# IMU.net
KiCad netlist of a schematic drawn in Altium Designer
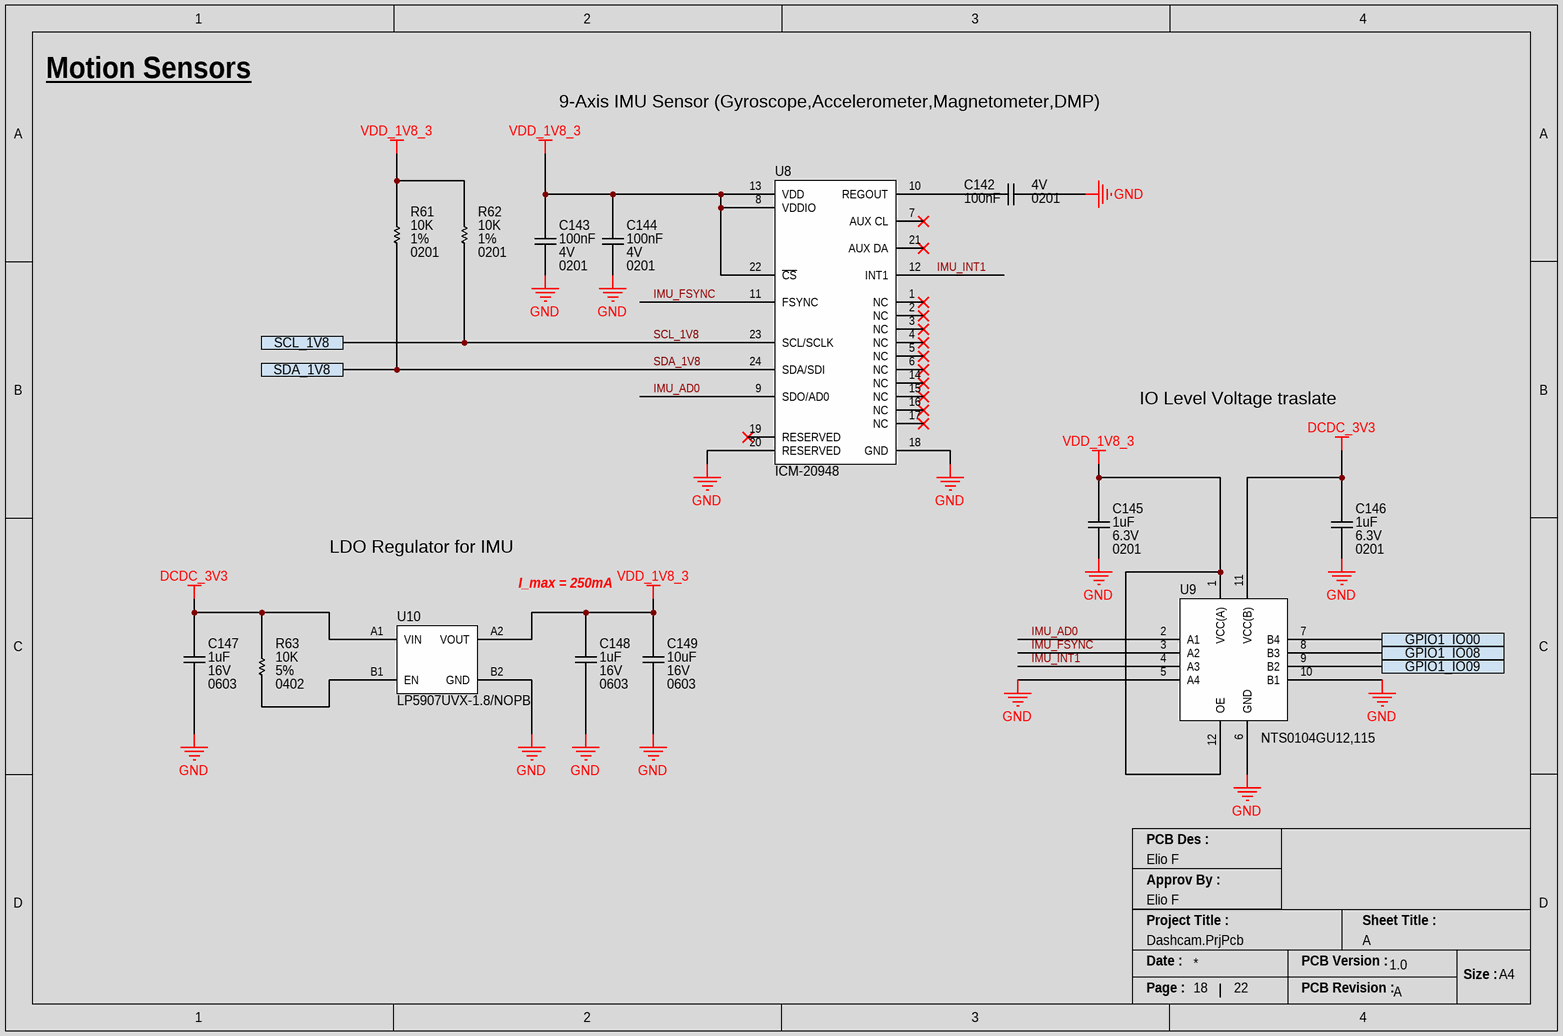
[diagram p0: IMU.SchDoc]

(export (version "E")
  (design (tool "Eeschema 10.0.6"))
  (components
    (comp (ref "C142")
      (value "C0201C104K7PAC7867")
      (footprint "CAP_0201_CAPC0603X03N")
      (description "SMD Comm X5R 0201 (0603Metric) ceramic capacitor 0.024Lx0.012W 0.60mmx0.30mm X5R ±10% 0.1muF")
      (fields
        (field (name "MANUFACTURER") "KEMET")
        (field (name "TOLERANCE") "10%")
        (field (name "VOLTAGE RATING") "4V")
        (field (name "CAPACITANCE") "100nF")
        (field (name "CASE/PACKAGE") "0201")
      )
      (libsource (lib "Electronic Devices_LIB") (part "CAP_100NF_4V_X5R_0201"))
    )
    (comp (ref "C143")
      (value "C0201C104K7PAC7867")
      (footprint "CAP_0201_CAPC0603X03N")
      (description "SMD Comm X5R 0201 (0603Metric) ceramic capacitor 0.024Lx0.012W 0.60mmx0.30mm X5R ±10% 0.1muF")
      (fields
        (field (name "MANUFACTURER") "KEMET")
        (field (name "TOLERANCE") "10%")
        (field (name "VOLTAGE RATING") "4V")
        (field (name "CAPACITANCE") "100nF")
        (field (name "CASE/PACKAGE") "0201")
      )
      (libsource (lib "Electronic Devices_LIB") (part "CAP_100NF_4V_X5R_0201"))
    )
    (comp (ref "C144")
      (value "C0201C104K7PAC7867")
      (footprint "CAP_0201_CAPC0603X03N")
      (description "SMD Comm X5R 0201 (0603Metric) ceramic capacitor 0.024Lx0.012W 0.60mmx0.30mm X5R ±10% 0.1muF")
      (fields
        (field (name "MANUFACTURER") "KEMET")
        (field (name "TOLERANCE") "10%")
        (field (name "VOLTAGE RATING") "4V")
        (field (name "CAPACITANCE") "100nF")
        (field (name "CASE/PACKAGE") "0201")
      )
      (libsource (lib "Electronic Devices_LIB") (part "CAP_100NF_4V_X5R_0201"))
    )
    (comp (ref "C145")
      (value "02016D105MAT2A")
      (footprint "CAP_0201_CAPC0603X03N")
      (description "0201 1 uF 6.3 V ±20 % Tolerance X5R Surface Mount Multilayer Ceramic Capacitor")
      (fields
        (field (name "MANUFACTURER") "Kyocera AVX")
        (field (name "TOLERANCE") "20%")
        (field (name "VOLTAGE RATING (DC)") "6.3V")
        (field (name "CAPACITANCE") "1uF")
        (field (name "CASE/PACKAGE") "0201")
      )
      (libsource (lib "Electronic Devices_LIB") (part "CAP_1UF_6.3V_X5R_0201"))
    )
    (comp (ref "C146")
      (value "02016D105MAT2A")
      (footprint "CAP_0201_CAPC0603X03N")
      (description "0201 1 uF 6.3 V ±20 % Tolerance X5R Surface Mount Multilayer Ceramic Capacitor")
      (fields
        (field (name "MANUFACTURER") "Kyocera AVX")
        (field (name "TOLERANCE") "20%")
        (field (name "VOLTAGE RATING (DC)") "6.3V")
        (field (name "CAPACITANCE") "1uF")
        (field (name "CASE/PACKAGE") "0201")
      )
      (libsource (lib "Electronic Devices_LIB") (part "CAP_1UF_6.3V_X5R_0201"))
    )
    (comp (ref "C147")
      (value "CL10A105KO8NNNC")
      (footprint "CAP_0603_CAPC1608X08N")
      (description "CAP CER 1UF 16V X5R 0603")
      (fields
        (field (name "MANUFACTURER") "Samsung")
        (field (name "TOLERANCE") "10%")
        (field (name "VOLTAGE RATING") "16V")
        (field (name "CAPACITANCE") "1uF")
        (field (name "CASE/PACKAGE") "0603")
      )
      (libsource (lib "Electronic Devices_LIB") (part "CAP_1UF_16V_X5R_0603"))
    )
    (comp (ref "C148")
      (value "CL10A105KO8NNNC")
      (footprint "CAP_0603_CAPC1608X08N")
      (description "CAP CER 1UF 16V X5R 0603")
      (fields
        (field (name "MANUFACTURER") "Samsung")
        (field (name "TOLERANCE") "10%")
        (field (name "VOLTAGE RATING") "16V")
        (field (name "CAPACITANCE") "1uF")
        (field (name "CASE/PACKAGE") "0603")
      )
      (libsource (lib "Electronic Devices_LIB") (part "CAP_1UF_16V_X5R_0603"))
    )
    (comp (ref "C149")
      (value "GRM188R61C106MAALD")
      (footprint "CAP_0603_CAPC1608X08N")
      (description "0603 10 uF 16 V ±20% Tolerance X5R Multilayer Ceramic Chip Capacitor")
      (fields
        (field (name "MANUFACTURER") "Murata")
        (field (name "TOLERANCE") "20%")
        (field (name "VOLTAGE RATING") "16V")
        (field (name "CAPACITANCE") "10uF")
        (field (name "CASE/PACKAGE") "0603")
      )
      (libsource (lib "Electronic Devices_LIB") (part "CAP_10UF_16V_X5R_0603"))
    )
    (comp (ref "R61")
      (value "RC0201FR-0710KL")
      (footprint "RES_0201_RESC0603X02N")
      (description "SMD Chip Resistor, 10 kOhm, ± 1%, 50 mW, 0201 [0603 Metric], Thick Film, General Purpose")
      (fields
        (field (name "MANUFACTURER") "Yageo")
        (field (name "TOLERANCE") "1%")
        (field (name "RESISTANCE") "10K")
        (field (name "CASE CODE (IMPERIAL)") "0201")
      )
      (libsource (lib "Electronic Devices_LIB") (part "RES_10K_1/12W_1%_0201"))
    )
    (comp (ref "R62")
      (value "RC0201FR-0710KL")
      (footprint "RES_0201_RESC0603X02N")
      (description "SMD Chip Resistor, 10 kOhm, ± 1%, 50 mW, 0201 [0603 Metric], Thick Film, General Purpose")
      (fields
        (field (name "MANUFACTURER") "Yageo")
        (field (name "TOLERANCE") "1%")
        (field (name "RESISTANCE") "10K")
        (field (name "CASE CODE (IMPERIAL)") "0201")
      )
      (libsource (lib "Electronic Devices_LIB") (part "RES_10K_1/12W_1%_0201"))
    )
    (comp (ref "R63")
      (value "ERJ-2GEJ103X")
      (footprint "RES_0402_RESC1005X04N")
      (description "Res Thick Film 0402 10K Ohm 5% 1/10W ±200ppm/°C Molded SMD Punched Carrier T/R")
      (fields
        (field (name "MANUFACTURER") "Panasonic")
        (field (name "TOLERANCE") "5%")
        (field (name "RESISTANCE") "10K")
        (field (name "CASE/PACKAGE") "0402")
      )
      (libsource (lib "Electronic Devices_LIB") (part "RES_10K_5%_100mW_0402"))
    )
    (comp (ref "U8")
      (value "ICM-20948")
      (footprint "IC_IMU_TDK_InvenSense_0_IPC_A")
      (description "IMU (Inertial Measurement Unit), 9-Axis, Accelerometer, Gyroscope, Compass")
      (fields (field (name "MANUFACTURER") "TDK"))
      (libsource (lib "Electronic Devices_LIB") (part "IC_IMU_9AXIS_ICM-20948"))
    )
    (comp (ref "U9")
      (value "NTS0104GU12,115")
      (footprint "IC_LEVEL_TRASLATOR_XQFN12_0P4_1P8X2P1")
      (description "NTS0104 Series 50 Mbps Dual Supply 3-ST O-DRN Translating Transceiver- XQFN-12")
      (fields (field (name "MANUFACTURER") "NXP Semiconductors"))
      (libsource (lib "Electronic Devices_LIB") (part "IC_LEVEL_TRASLATOR_NTS0104GU12,115"))
    )
    (comp (ref "U10")
      (value "LP5907UVX-1.8/NOPB")
      (footprint "IC_REG_LDO_BGA4C35P2X2_71X71X40")
      (description "Low Dropout Regulators(LDO) Positive Fixed 200mV @ 250mA 5.5V 1.8V 250mA DSBGA-4 RoHS")
      (fields (field (name "MANUFACTURER") "Texas Instruments"))
      (libsource (lib "Electronic Devices_LIB") (part "IC_REG_LDO_1.8V_250mA_LP5907UVX-1.8/NOPB"))
    )
  )
  (nets
    (net (code "1") (name "/GPIO1_IO00") (class "Default")
      (node (ref "U9") (pin "7") (pinfunction "B4_7") (pintype "passive"))
    )
    (net (code "2") (name "/GPIO1_IO08") (class "Default")
      (node (ref "U9") (pin "8") (pinfunction "B3_8") (pintype "passive"))
    )
    (net (code "3") (name "/GPIO1_IO09") (class "Default")
      (node (ref "U9") (pin "9") (pinfunction "B2_9") (pintype "passive"))
    )
    (net (code "4") (name "/IMU_AD0") (class "Default")
      (node (ref "U8") (pin "9") (pinfunction "SDO/AD0_9") (pintype "passive"))
      (node (ref "U9") (pin "2") (pinfunction "A1_2") (pintype "passive"))
    )
    (net (code "5") (name "/IMU_FSYNC") (class "Default")
      (node (ref "U8") (pin "11") (pinfunction "FSYNC_11") (pintype "passive"))
      (node (ref "U9") (pin "3") (pinfunction "A2_3") (pintype "passive"))
    )
    (net (code "6") (name "/IMU_INT1") (class "Default")
      (node (ref "U8") (pin "12") (pinfunction "INT1_12") (pintype "passive"))
      (node (ref "U9") (pin "4") (pinfunction "A3_4") (pintype "passive"))
    )
    (net (code "7") (name "/SCL_1V8") (class "Default")
      (node (ref "R62") (pin "1") (pinfunction "1_1") (pintype "passive"))
      (node (ref "U8") (pin "23") (pinfunction "SCL/SCLK_23") (pintype "passive"))
    )
    (net (code "8") (name "/SDA_1V8") (class "Default")
      (node (ref "R61") (pin "1") (pinfunction "1_1") (pintype "passive"))
      (node (ref "U8") (pin "24") (pinfunction "SDA/SDI_24") (pintype "passive"))
    )
    (net (code "9") (name "DCDC_3V3") (class "Default")
      (node (ref "C146") (pin "2") (pinfunction "2_2") (pintype "passive"))
      (node (ref "C147") (pin "2") (pinfunction "2_2") (pintype "passive"))
      (node (ref "R63") (pin "2") (pinfunction "2_2") (pintype "passive"))
      (node (ref "U10") (pin "A1") (pinfunction "VIN_A1") (pintype "passive"))
      (node (ref "U9") (pin "11") (pinfunction "VCC(B)_11") (pintype "passive"))
    )
    (net (code "10") (name "GND") (class "Default")
      (node (ref "C142") (pin "1") (pinfunction "1_1") (pintype "passive"))
      (node (ref "C143") (pin "1") (pinfunction "1_1") (pintype "passive"))
      (node (ref "C144") (pin "1") (pinfunction "1_1") (pintype "passive"))
      (node (ref "C145") (pin "1") (pinfunction "1_1") (pintype "passive"))
      (node (ref "C146") (pin "1") (pinfunction "1_1") (pintype "passive"))
      (node (ref "C147") (pin "1") (pinfunction "1_1") (pintype "passive"))
      (node (ref "C148") (pin "1") (pinfunction "1_1") (pintype "passive"))
      (node (ref "C149") (pin "1") (pinfunction "1_1") (pintype "passive"))
      (node (ref "U10") (pin "B2") (pinfunction "GND_B2") (pintype "passive"))
      (node (ref "U8") (pin "18") (pinfunction "GND_18") (pintype "power_in"))
      (node (ref "U8") (pin "20") (pinfunction "RESERVED_20") (pintype "passive"))
      (node (ref "U9") (pin "10") (pinfunction "B1_10") (pintype "passive"))
      (node (ref "U9") (pin "5") (pinfunction "A4_5") (pintype "passive"))
      (node (ref "U9") (pin "6") (pinfunction "GND_6") (pintype "passive"))
    )
    (net (code "11") (name "Net-(U8-REGOUT)") (class "Default")
      (node (ref "C142") (pin "2") (pinfunction "2_2") (pintype "passive"))
      (node (ref "U8") (pin "10") (pinfunction "REGOUT_10") (pintype "passive"))
    )
    (net (code "12") (name "Net-(U10-EN)") (class "Default")
      (node (ref "R63") (pin "1") (pinfunction "1_1") (pintype "passive"))
      (node (ref "U10") (pin "B1") (pinfunction "EN_B1") (pintype "passive"))
    )
    (net (code "13") (name "VDD_1V8_3") (class "Default")
      (node (ref "C143") (pin "2") (pinfunction "2_2") (pintype "passive"))
      (node (ref "C144") (pin "2") (pinfunction "2_2") (pintype "passive"))
      (node (ref "C145") (pin "2") (pinfunction "2_2") (pintype "passive"))
      (node (ref "C148") (pin "2") (pinfunction "2_2") (pintype "passive"))
      (node (ref "C149") (pin "2") (pinfunction "2_2") (pintype "passive"))
      (node (ref "R61") (pin "2") (pinfunction "2_2") (pintype "passive"))
      (node (ref "R62") (pin "2") (pinfunction "2_2") (pintype "passive"))
      (node (ref "U10") (pin "A2") (pinfunction "VOUT_A2") (pintype "passive"))
      (node (ref "U8") (pin "13") (pinfunction "VDD_13") (pintype "power_in"))
      (node (ref "U8") (pin "22") (pinfunction "~{CS}_22") (pintype "passive"))
      (node (ref "U8") (pin "8") (pinfunction "VDDIO_8") (pintype "power_in"))
      (node (ref "U9") (pin "1") (pinfunction "VCC(A)_1") (pintype "passive"))
      (node (ref "U9") (pin "12") (pinfunction "OE_12") (pintype "passive"))
    )
    (net (code "14") (name "unconnected-(U8-AUX_CL-Pad7)") (class "Default")
      (node (ref "U8") (pin "7") (pinfunction "AUX_CL_7") (pintype "passive+no_connect"))
    )
    (net (code "15") (name "unconnected-(U8-AUX_DA-Pad21)") (class "Default")
      (node (ref "U8") (pin "21") (pinfunction "AUX_DA_21") (pintype "passive+no_connect"))
    )
    (net (code "16") (name "unconnected-(U8-NC-Pad1)") (class "Default")
      (node (ref "U8") (pin "1") (pinfunction "NC_1") (pintype "passive+no_connect"))
    )
    (net (code "17") (name "unconnected-(U8-NC-Pad2)") (class "Default")
      (node (ref "U8") (pin "2") (pinfunction "NC_2") (pintype "passive+no_connect"))
    )
    (net (code "18") (name "unconnected-(U8-NC-Pad3)") (class "Default")
      (node (ref "U8") (pin "3") (pinfunction "NC_3") (pintype "passive+no_connect"))
    )
    (net (code "19") (name "unconnected-(U8-NC-Pad4)") (class "Default")
      (node (ref "U8") (pin "4") (pinfunction "NC_4") (pintype "passive+no_connect"))
    )
    (net (code "20") (name "unconnected-(U8-NC-Pad5)") (class "Default")
      (node (ref "U8") (pin "5") (pinfunction "NC_5") (pintype "passive+no_connect"))
    )
    (net (code "21") (name "unconnected-(U8-NC-Pad6)") (class "Default")
      (node (ref "U8") (pin "6") (pinfunction "NC_6") (pintype "passive+no_connect"))
    )
    (net (code "22") (name "unconnected-(U8-NC-Pad14)") (class "Default")
      (node (ref "U8") (pin "14") (pinfunction "NC_14") (pintype "passive+no_connect"))
    )
    (net (code "23") (name "unconnected-(U8-NC-Pad15)") (class "Default")
      (node (ref "U8") (pin "15") (pinfunction "NC_15") (pintype "passive+no_connect"))
    )
    (net (code "24") (name "unconnected-(U8-NC-Pad16)") (class "Default")
      (node (ref "U8") (pin "16") (pinfunction "NC_16") (pintype "passive+no_connect"))
    )
    (net (code "25") (name "unconnected-(U8-NC-Pad17)") (class "Default")
      (node (ref "U8") (pin "17") (pinfunction "NC_17") (pintype "passive+no_connect"))
    )
    (net (code "26") (name "unconnected-(U8-RESERVED-Pad19)") (class "Default")
      (node (ref "U8") (pin "19") (pinfunction "RESERVED_19") (pintype "passive+no_connect"))
    )
  )
)
